# RectifierPartTwo.net
KiCad netlist of a schematic drawn in EAGLE
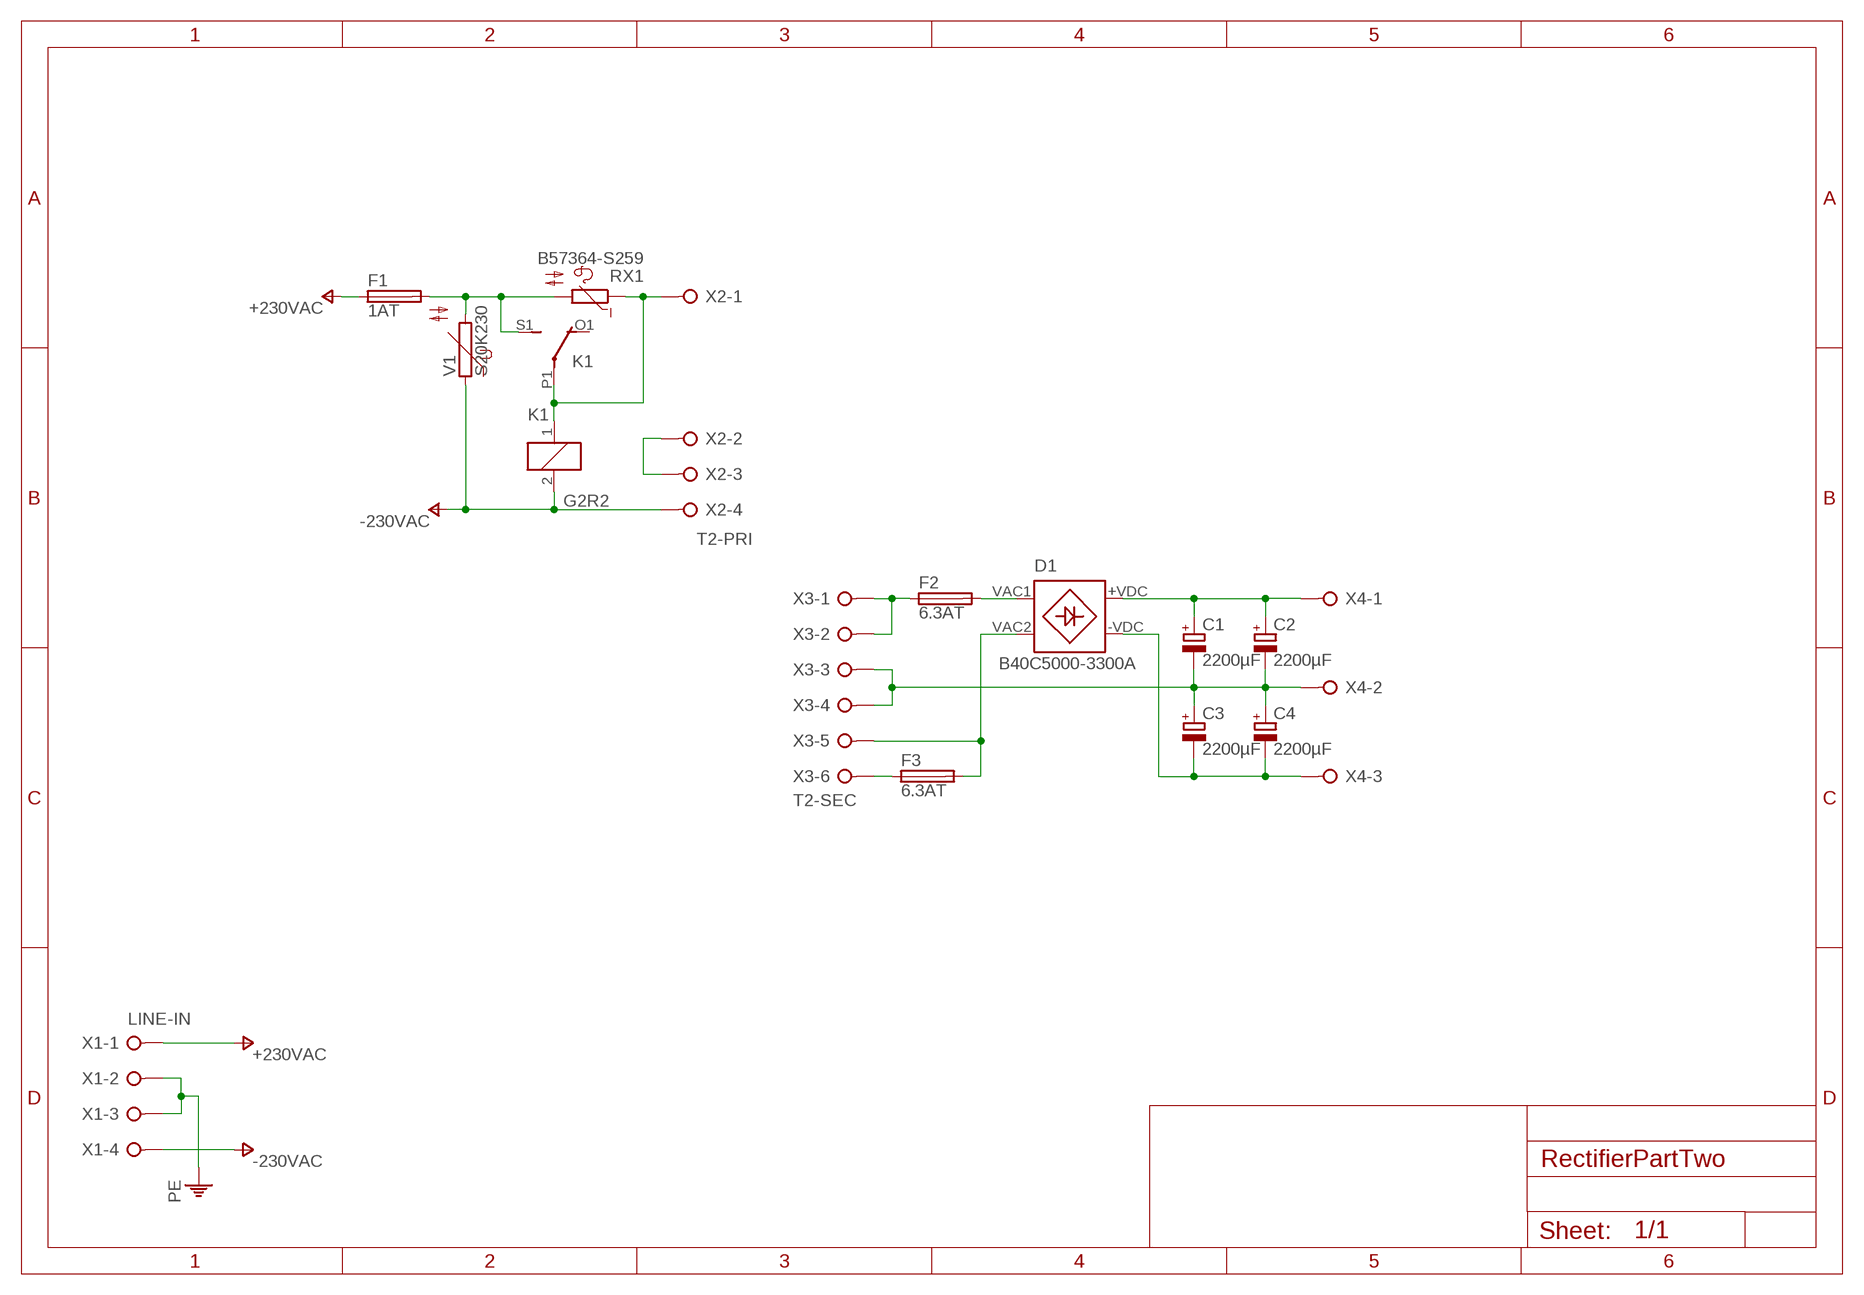
[diagram p0: schematic, sheet 1]

(export (version "E")
  (design (tool "Eeschema 10.0.6"))
  (components
    (comp (ref "C1")
      (value "2200µF")
      (footprint "eagle-import:E7,5-16")
      (libsource (lib "eagle-import") (part "CPOL-EUE7.5-16"))
    )
    (comp (ref "C2")
      (value "2200µF")
      (footprint "eagle-import:E7,5-16")
      (libsource (lib "eagle-import") (part "CPOL-EUE7.5-16"))
    )
    (comp (ref "C3")
      (value "2200µF")
      (footprint "eagle-import:E7,5-16")
      (libsource (lib "eagle-import") (part "CPOL-EUE7.5-16"))
    )
    (comp (ref "C4")
      (value "2200µF")
      (footprint "eagle-import:E7,5-16")
      (libsource (lib "eagle-import") (part "CPOL-EUE7.5-16"))
    )
    (comp (ref "D1")
      (value "B40C5000-3300A")
      (footprint "eagle-import:B..C")
      (libsource (lib "eagle-import") (part "B40C5000-3300A"))
    )
    (comp (ref "F1")
      (value "1AT")
      (footprint "eagle-import:SH22,5A")
      (fields (field (name "MPN") "0031.7701.11"))
      (libsource (lib "eagle-import") (part "SH22,5A"))
    )
    (comp (ref "F2")
      (value "6.3AT")
      (footprint "eagle-import:SH22,5A")
      (fields (field (name "MPN") "0031.7701.11"))
      (libsource (lib "eagle-import") (part "SH22,5A"))
    )
    (comp (ref "F3")
      (value "6.3AT")
      (footprint "eagle-import:SH22,5A")
      (fields (field (name "MPN") "0031.7701.11"))
      (libsource (lib "eagle-import") (part "SH22,5A"))
    )
    (comp (ref "K1")
      (value "G2R2")
      (footprint "eagle-import:G2R2")
      (fields (field (name "MF") "OMRON COMPONENTS USA") (field (name "MPN") "G2R-2-DC6"))
      (libsource (lib "eagle-import") (part "G2R2"))
    )
    (comp (ref "RX1")
      (value "B57364-S259")
      (footprint "eagle-import:B57364S0")
      (libsource (lib "eagle-import") (part "EPCB57364-S259"))
    )
    (comp (ref "V1")
      (value "S20K230")
      (footprint "eagle-import:S20K230")
      (libsource (lib "eagle-import") (part "S20K230"))
    )
    (comp (ref "X1")
      (value "LINE-IN")
      (footprint "eagle-import:W237-4P")
      (libsource (lib "eagle-import") (part "W237-04P"))
    )
    (comp (ref "X2")
      (value "T2-PRI")
      (footprint "eagle-import:W237-4P")
      (libsource (lib "eagle-import") (part "W237-04P"))
    )
    (comp (ref "X3")
      (value "T2-SEC")
      (footprint "eagle-import:W237-6P")
      (libsource (lib "eagle-import") (part "W237-06P"))
    )
    (comp (ref "X4")
      (value "W237-03P")
      (footprint "eagle-import:W237-133")
      (libsource (lib "eagle-import") (part "W237-03P"))
    )
  )
  (nets
    (net (code "1") (name "+230VAC") (class "Default")
      (node (ref "F1") (pin "1") (pinfunction "1_1") (pintype "passive"))
      (node (ref "X1") (pin "1") (pinfunction "KL_1") (pintype "passive"))
    )
    (net (code "2") (name "-230VAC") (class "Default")
      (node (ref "K1") (pin "2") (pinfunction "2_2") (pintype "passive"))
      (node (ref "V1") (pin "1") (pinfunction "1_1") (pintype "passive"))
      (node (ref "X1") (pin "4") (pinfunction "KL_4") (pintype "passive"))
      (node (ref "X2") (pin "4") (pinfunction "KL_4") (pintype "passive"))
    )
    (net (code "3") (name "Net-(D1-PadVAC1)") (class "Default")
      (node (ref "D1") (pin "VAC1") (pinfunction "VAC1_VAC1") (pintype "input"))
      (node (ref "F2") (pin "2") (pinfunction "2_2") (pintype "passive"))
    )
    (net (code "4") (name "Net-(K1B-P)") (class "Default")
      (node (ref "K1") (pin "1") (pinfunction "1_1") (pintype "passive"))
      (node (ref "K1") (pin "P1") (pinfunction "P_P1") (pintype "passive"))
      (node (ref "RX1") (pin "P$1") (pinfunction "1_P$1") (pintype "passive"))
      (node (ref "X2") (pin "1") (pinfunction "KL_1") (pintype "passive"))
    )
    (net (code "5") (name "Net-(K1B-S)") (class "Default")
      (node (ref "F1") (pin "2") (pinfunction "2_2") (pintype "passive"))
      (node (ref "K1") (pin "S1") (pinfunction "S_S1") (pintype "passive"))
      (node (ref "RX1") (pin "P$2") (pinfunction "2_P$2") (pintype "passive"))
      (node (ref "V1") (pin "2") (pinfunction "2_2") (pintype "passive"))
    )
    (net (code "6") (name "Net-(X2B-KL)") (class "Default")
      (node (ref "X2") (pin "2") (pinfunction "KL_2") (pintype "passive"))
      (node (ref "X2") (pin "3") (pinfunction "KL_3") (pintype "passive"))
    )
    (net (code "7") (name "Net-(X3A-KL)") (class "Default")
      (node (ref "F2") (pin "1") (pinfunction "1_1") (pintype "passive"))
      (node (ref "X3") (pin "1") (pinfunction "KL_1") (pintype "passive"))
      (node (ref "X3") (pin "2") (pinfunction "KL_2") (pintype "passive"))
    )
    (net (code "8") (name "Net-(X3C-KL)") (class "Default")
      (node (ref "C1") (pin "-") (pinfunction "-_-") (pintype "passive"))
      (node (ref "C2") (pin "-") (pinfunction "-_-") (pintype "passive"))
      (node (ref "C3") (pin "+") (pinfunction "+_+") (pintype "passive"))
      (node (ref "C4") (pin "+") (pinfunction "+_+") (pintype "passive"))
      (node (ref "X3") (pin "3") (pinfunction "KL_3") (pintype "passive"))
      (node (ref "X3") (pin "4") (pinfunction "KL_4") (pintype "passive"))
      (node (ref "X4") (pin "2") (pinfunction "KL_2") (pintype "passive"))
    )
    (net (code "9") (name "Net-(X3E-KL)") (class "Default")
      (node (ref "D1") (pin "VAC2") (pinfunction "VAC2_VAC2") (pintype "input"))
      (node (ref "F3") (pin "2") (pinfunction "2_2") (pintype "passive"))
      (node (ref "X3") (pin "5") (pinfunction "KL_5") (pintype "passive"))
    )
    (net (code "10") (name "Net-(X3F-KL)") (class "Default")
      (node (ref "F3") (pin "1") (pinfunction "1_1") (pintype "passive"))
      (node (ref "X3") (pin "6") (pinfunction "KL_6") (pintype "passive"))
    )
    (net (code "11") (name "Net-(X4A-KL)") (class "Default")
      (node (ref "C1") (pin "+") (pinfunction "+_+") (pintype "passive"))
      (node (ref "C2") (pin "+") (pinfunction "+_+") (pintype "passive"))
      (node (ref "D1") (pin "+VDC") (pinfunction "+VDC_+VDC") (pintype "output"))
      (node (ref "X4") (pin "1") (pinfunction "KL_1") (pintype "passive"))
    )
    (net (code "12") (name "Net-(X4C-KL)") (class "Default")
      (node (ref "C3") (pin "-") (pinfunction "-_-") (pintype "passive"))
      (node (ref "C4") (pin "-") (pinfunction "-_-") (pintype "passive"))
      (node (ref "D1") (pin "-VDC") (pinfunction "-VDC_-VDC") (pintype "output"))
      (node (ref "X4") (pin "3") (pinfunction "KL_3") (pintype "passive"))
    )
    (net (code "13") (name "PE") (class "Default")
      (node (ref "X1") (pin "2") (pinfunction "KL_2") (pintype "passive"))
      (node (ref "X1") (pin "3") (pinfunction "KL_3") (pintype "passive"))
    )
    (net (code "14") (name "unconnected-(K1B-O-PadO1)") (class "Default")
      (node (ref "K1") (pin "O1") (pinfunction "O_O1") (pintype "passive"))
    )
  )
)
